# Version1_3.net
KiCad netlist of a schematic drawn in Altium Designer
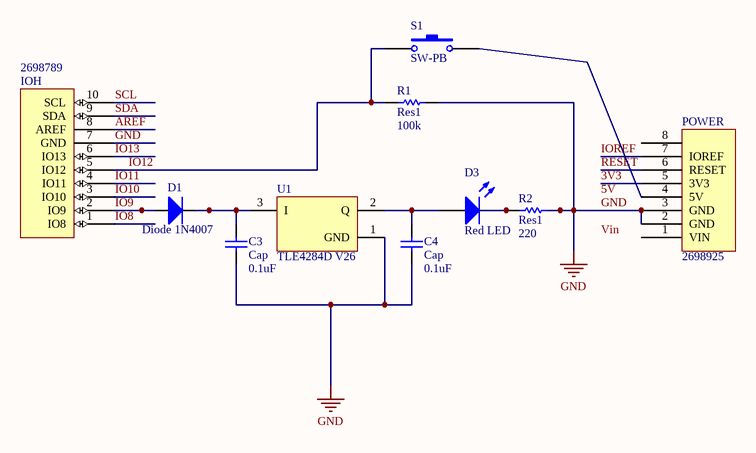
[diagram p0: Version1.3.SchDoc]

(export (version "E")
  (design (tool "Eeschema 10.0.6"))
  (components
    (comp (ref "C3")
      (value "Cap")
      (footprint "RAD-0.3")
      (description "Capacitor")
      (fields (field (name "ALTIUM_VALUE") "0.1uF") (field (name "PUBLISHER") "Altium Limited"))
      (libsource (lib "Miscellaneous Devices") (part "Cap"))
    )
    (comp (ref "C4")
      (value "Cap")
      (footprint "RAD-0.3")
      (description "Capacitor")
      (fields (field (name "ALTIUM_VALUE") "0.1uF") (field (name "PUBLISHER") "Altium Limited"))
      (libsource (lib "Miscellaneous Devices") (part "Cap"))
    )
    (comp (ref "D1")
      (value "Diode 1N4007")
      (footprint "DO-41")
      (description "1 Amp General Purpose Rectifier")
      (fields (field (name "PUBLISHER") "Altium Limited"))
      (libsource (lib "Miscellaneous Devices") (part "Diode 1N4007"))
    )
    (comp (ref "D3")
      (value "Red LED")
      (footprint "3.2X1.6X1.1")
      (description "Typical RED, GREEN, YELLOW, AMBER GaAs LED")
      (fields (field (name "PUBLISHER") "Altium Limited"))
      (libsource (lib "Miscellaneous Devices") (part "LED2"))
    )
    (comp (ref "IOH")
      (value "IOH")
      (footprint "Header:Header 10x1 8.5mm")
      (fields (field (name "SUPPLIER PART NUMBER 3") "2698789"))
      (libsource (lib "Header") (part "IOH"))
    )
    (comp (ref "POWER")
      (value "POWER_UNO")
      (footprint "Header 8x1 8.5mm")
      (fields (field (name "SUPPLIER PART NUMBER 4") "2698925"))
      (libsource (lib "Header") (part "POWER_UNO"))
    )
    (comp (ref "R1")
      (value "Res1")
      (footprint "AXIAL-0.3")
      (description "Resistor")
      (fields (field (name "ALTIUM_VALUE") "100k") (field (name "PUBLISHER") "Altium Limited"))
      (libsource (lib "Miscellaneous Devices") (part "Res1"))
    )
    (comp (ref "R2")
      (value "Res1")
      (footprint "AXIAL-0.3")
      (description "Resistor")
      (fields (field (name "ALTIUM_VALUE") "220") (field (name "PUBLISHER") "Altium Limited"))
      (libsource (lib "Miscellaneous Devices") (part "Res1"))
    )
    (comp (ref "S1")
      (value "SW-PB")
      (footprint "SPST-2")
      (description "Switch")
      (fields (field (name "PUBLISHER") "Altium Limited"))
      (libsource (lib "Miscellaneous Devices") (part "SW-PB"))
    )
    (comp (ref "U1")
      (value "TLE4284D V26")
      (footprint "INF-PG-TO252-3-11_N")
      (description "Voltage Regulator, 4 to 40 V Supply, 2.6 V Output, -40 to 150 degC, PG-TO252-3-11, Reel, Green")
      (fields (field (name "MANUFACTURER") "Infineon"))
      (libsource (lib "Infineon_Power_Supply_Voltage_Regulator") (part "TLE4284D V26"))
    )
  )
  (nets
    (net (code "1") (name "/3V3") (class "Default")
      (node (ref "POWER") (pin "5") (pinfunction "3V3_5") (pintype "power_in"))
    )
    (net (code "4") (name "/AREF") (class "Default")
      (node (ref "IOH") (pin "8") (pinfunction "AREF_8") (pintype "passive"))
    )
    (net (code "5") (name "/IO8") (class "Default")
      (node (ref "IOH") (pin "1") (pinfunction "IO8_1") (pintype "bidirectional"))
    )
    (net (code "6") (name "/IO9") (class "Default")
      (node (ref "D1") (pin "1") (pinfunction "A_1") (pintype "passive"))
      (node (ref "IOH") (pin "2") (pinfunction "IO9_2") (pintype "bidirectional"))
    )
    (net (code "7") (name "/IO10") (class "Default")
      (node (ref "IOH") (pin "3") (pinfunction "IO10_3") (pintype "bidirectional"))
    )
    (net (code "8") (name "/IO11") (class "Default")
      (node (ref "IOH") (pin "4") (pinfunction "IO11_4") (pintype "bidirectional"))
    )
    (net (code "9") (name "/IO12") (class "Default")
      (node (ref "IOH") (pin "5") (pinfunction "IO12_5") (pintype "bidirectional"))
      (node (ref "R1") (pin "1") (pinfunction "1_1") (pintype "passive"))
      (node (ref "S1") (pin "1") (pinfunction "1_1") (pintype "passive"))
    )
    (net (code "10") (name "/IO13") (class "Default")
      (node (ref "IOH") (pin "6") (pinfunction "IO13_6") (pintype "bidirectional"))
    )
    (net (code "11") (name "/IOREF") (class "Default")
      (node (ref "POWER") (pin "7") (pinfunction "IOREF_7") (pintype "power_in"))
    )
    (net (code "12") (name "/RESET") (class "Default")
      (node (ref "POWER") (pin "6") (pinfunction "RESET_6") (pintype "passive"))
    )
    (net (code "13") (name "/SCL") (class "Default")
      (node (ref "IOH") (pin "10") (pinfunction "SCL_10") (pintype "bidirectional"))
    )
    (net (code "14") (name "/SDA") (class "Default")
      (node (ref "IOH") (pin "9") (pinfunction "SDA_9") (pintype "bidirectional"))
    )
    (net (code "16") (name "GND") (class "Default")
      (node (ref "C3") (pin "1") (pinfunction "1_1") (pintype "passive"))
      (node (ref "C4") (pin "1") (pinfunction "1_1") (pintype "passive"))
      (node (ref "IOH") (pin "7") (pinfunction "GND_7") (pintype "power_in"))
      (node (ref "POWER") (pin "2") (pinfunction "GND_2") (pintype "power_in"))
      (node (ref "POWER") (pin "3") (pinfunction "GND_3") (pintype "power_in"))
      (node (ref "R1") (pin "2") (pinfunction "2_2") (pintype "passive"))
      (node (ref "R2") (pin "2") (pinfunction "2_2") (pintype "passive"))
      (node (ref "U1") (pin "1") (pinfunction "GND_1") (pintype "power_in"))
    )
    (net (code "17") (name "Net-(D1-K)") (class "Default")
      (node (ref "C3") (pin "2") (pinfunction "2_2") (pintype "passive"))
      (node (ref "D1") (pin "2") (pinfunction "K_2") (pintype "passive"))
      (node (ref "U1") (pin "3") (pinfunction "I_3") (pintype "power_in"))
    )
    (net (code "18") (name "Net-(D3-A)") (class "Default")
      (node (ref "C4") (pin "2") (pinfunction "2_2") (pintype "passive"))
      (node (ref "D3") (pin "1") (pinfunction "A_1") (pintype "passive"))
      (node (ref "U1") (pin "2") (pinfunction "Q_2") (pintype "power_in"))
    )
    (net (code "19") (name "Net-(D3-K)") (class "Default")
      (node (ref "D3") (pin "2") (pinfunction "K_2") (pintype "passive"))
      (node (ref "R2") (pin "1") (pinfunction "1_1") (pintype "passive"))
    )
    (net (code "20") (name "Net-(POWER-5V)") (class "Default")
      (node (ref "POWER") (pin "4") (pinfunction "5V_4") (pintype "power_in"))
      (node (ref "S1") (pin "2") (pinfunction "2_2") (pintype "passive"))
    )
    (net (code "21") (name "unconnected-(POWER-Pad8)") (class "Default")
      (node (ref "POWER") (pin "8") (pintype "passive"))
    )
    (net (code "22") (name "unconnected-(POWER-VIN-Pad1)") (class "Default")
      (node (ref "POWER") (pin "1") (pinfunction "VIN_1") (pintype "power_in"))
    )
  )
)
